# DC_DC_V1_4_2-1_top_with_comments.net
KiCad netlist of a schematic drawn in EAGLE
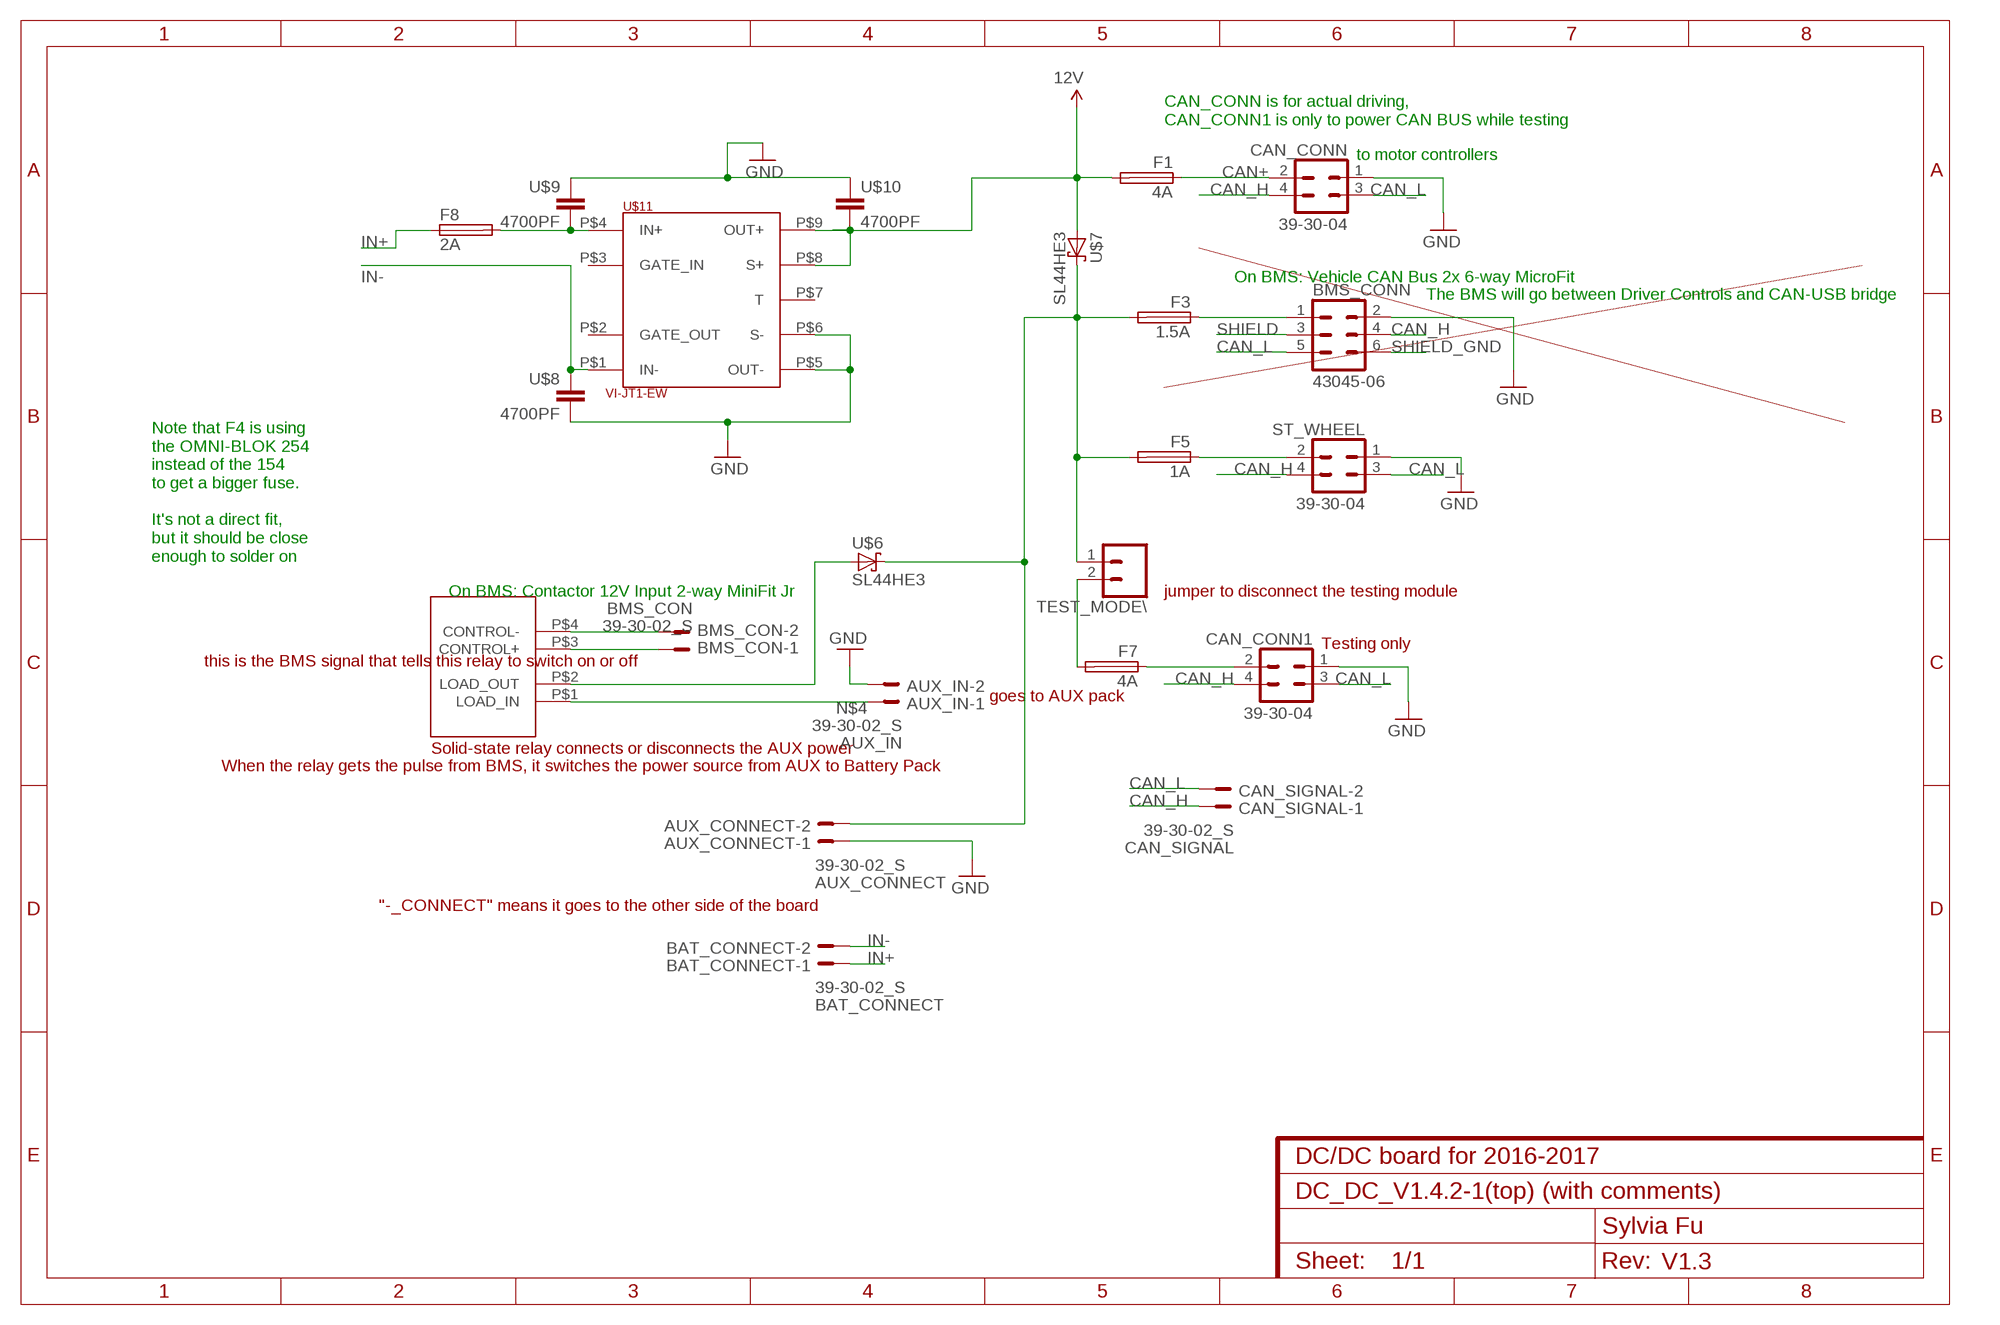
[diagram p0: schematic, sheet 1]

(export (version "E")
  (design (tool "Eeschema 10.0.6"))
  (components
    (comp (ref "AUX_CONNECT")
      (value "39-30-02_S")
      (footprint "eagle-import:39-30-_02_")
      (libsource (lib "eagle-import") (part "39-30-?02?_S"))
    )
    (comp (ref "AUX_IN")
      (value "39-30-02_S")
      (footprint "eagle-import:39-30-_02_")
      (libsource (lib "eagle-import") (part "39-30-?02?_S"))
    )
    (comp (ref "BAT_CONNECT")
      (value "39-30-02_S")
      (footprint "eagle-import:39-30-_02_")
      (libsource (lib "eagle-import") (part "39-30-?02?_S"))
    )
    (comp (ref "BMS_CON")
      (value "39-30-02_S")
      (footprint "eagle-import:39-30-_02_")
      (libsource (lib "eagle-import") (part "39-30-?02?_S"))
    )
    (comp (ref "BMS_CONN")
      (value "43045-06")
      (footprint "eagle-import:43045-06")
      (libsource (lib "eagle-import") (part "43045-06"))
    )
    (comp (ref "CAN_CONN")
      (value "39-30-04")
      (footprint "eagle-import:39-30-_04_")
      (libsource (lib "eagle-import") (part "39-30-?04?"))
    )
    (comp (ref "CAN_CONN1")
      (value "39-30-04")
      (footprint "eagle-import:39-30-_04_")
      (libsource (lib "eagle-import") (part "39-30-?04?"))
    )
    (comp (ref "CAN_SIGNAL")
      (value "39-30-02_S")
      (footprint "eagle-import:39-30-_02_")
      (libsource (lib "eagle-import") (part "39-30-?02?_S"))
    )
    (comp (ref "F1")
      (value "4A")
      (footprint "eagle-import:OMNIBLOK")
      (libsource (lib "eagle-import") (part "SMD-MICRO-FUSE-BLOCK"))
    )
    (comp (ref "F3")
      (value "1.5A")
      (footprint "eagle-import:OMNIBLOK")
      (libsource (lib "eagle-import") (part "SMD-MICRO-FUSE-BLOCK"))
    )
    (comp (ref "F5")
      (value "1A")
      (footprint "eagle-import:OMNIBLOK")
      (libsource (lib "eagle-import") (part "SMD-MICRO-FUSE-BLOCK"))
    )
    (comp (ref "F7")
      (value "4A")
      (footprint "eagle-import:OMNIBLOK")
      (libsource (lib "eagle-import") (part "SMD-MICRO-FUSE-BLOCK"))
    )
    (comp (ref "F8")
      (value "2A")
      (footprint "eagle-import:OMNIBLOK")
      (libsource (lib "eagle-import") (part "SMD-MICRO-FUSE-BLOCK"))
    )
    (comp (ref "ST_WHEEL")
      (value "39-30-04")
      (footprint "eagle-import:39-30-_04_")
      (libsource (lib "eagle-import") (part "39-30-?04?"))
    )
    (comp (ref "TEST_MODE\\")
      (value "CONN_02")
      (footprint "eagle-import:1X02")
      (libsource (lib "eagle-import") (part "CONN_02"))
    )
    (comp (ref "U$2")
      (value "MPDCD3B")
      (footprint "eagle-import:MPDCD3B")
      (libsource (lib "eagle-import") (part "MPDCD3B"))
    )
    (comp (ref "U$6")
      (value "SL44HE3")
      (footprint "eagle-import:SMC")
      (libsource (lib "eagle-import") (part "SL44HE3"))
    )
    (comp (ref "U$7")
      (value "SL44HE3")
      (footprint "eagle-import:SMC")
      (libsource (lib "eagle-import") (part "SL44HE3"))
    )
    (comp (ref "U$8")
      (value "4700PF")
      (footprint "eagle-import:Y2_CAP")
      (libsource (lib "eagle-import") (part "4700PF"))
    )
    (comp (ref "U$9")
      (value "4700PF")
      (footprint "eagle-import:Y2_CAP")
      (libsource (lib "eagle-import") (part "4700PF"))
    )
    (comp (ref "U$10")
      (value "4700PF")
      (footprint "eagle-import:Y2_CAP")
      (libsource (lib "eagle-import") (part "4700PF"))
    )
    (comp (ref "U$11")
      (value "VI-JT1-EW")
      (footprint "eagle-import:VI-J00")
      (libsource (lib "eagle-import") (part "VI-JT1-EW"))
    )
  )
  (nets
    (net (code "1") (name "/CAN+") (class "Default")
      (node (ref "CAN_CONN") (pin "2") (pinfunction "2_2") (pintype "passive"))
      (node (ref "F1") (pin "P$1") (pinfunction "1_P$1") (pintype "passive"))
    )
    (net (code "2") (name "/CAN_H") (class "Default")
      (node (ref "BMS_CONN") (pin "4") (pinfunction "4_4") (pintype "passive"))
      (node (ref "CAN_CONN") (pin "4") (pinfunction "4_4") (pintype "passive"))
      (node (ref "CAN_CONN1") (pin "4") (pinfunction "4_4") (pintype "passive"))
      (node (ref "CAN_SIGNAL") (pin "1") (pinfunction "P_1") (pintype "passive"))
      (node (ref "ST_WHEEL") (pin "4") (pinfunction "4_4") (pintype "passive"))
    )
    (net (code "3") (name "/CAN_L") (class "Default")
      (node (ref "BMS_CONN") (pin "5") (pinfunction "5_5") (pintype "passive"))
      (node (ref "CAN_CONN") (pin "3") (pinfunction "3_3") (pintype "passive"))
      (node (ref "CAN_CONN1") (pin "3") (pinfunction "3_3") (pintype "passive"))
      (node (ref "CAN_SIGNAL") (pin "2") (pinfunction "P_2") (pintype "passive"))
      (node (ref "ST_WHEEL") (pin "3") (pinfunction "3_3") (pintype "passive"))
    )
    (net (code "4") (name "/IN+") (class "Default")
      (node (ref "BAT_CONNECT") (pin "1") (pinfunction "P_1") (pintype "passive"))
      (node (ref "F8") (pin "P$1") (pinfunction "1_P$1") (pintype "passive"))
    )
    (net (code "5") (name "/IN-") (class "Default")
      (node (ref "BAT_CONNECT") (pin "2") (pinfunction "P_2") (pintype "passive"))
      (node (ref "U$11") (pin "P$1") (pinfunction "IN-_P$1") (pintype "bidirectional"))
      (node (ref "U$8") (pin "P$1") (pinfunction "1_P$1") (pintype "passive"))
    )
    (net (code "6") (name "/N$4") (class "Default")
      (node (ref "U$2") (pin "P$2") (pinfunction "LOAD_OUT_P$2") (pintype "bidirectional"))
      (node (ref "U$6") (pin "A") (pinfunction "A_A") (pintype "passive"))
    )
    (net (code "7") (name "/SHIELD") (class "Default")
      (node (ref "BMS_CONN") (pin "3") (pinfunction "3_3") (pintype "passive"))
    )
    (net (code "8") (name "/SHIELD_GND") (class "Default")
      (node (ref "BMS_CONN") (pin "6") (pinfunction "6_6") (pintype "passive"))
    )
    (net (code "9") (name "12V") (class "Default")
      (node (ref "F1") (pin "P$2") (pinfunction "2_P$2") (pintype "passive"))
      (node (ref "U$10") (pin "P$2") (pinfunction "2_P$2") (pintype "passive"))
      (node (ref "U$11") (pin "P$8") (pinfunction "S+_P$8") (pintype "bidirectional"))
      (node (ref "U$11") (pin "P$9") (pinfunction "OUT+_P$9") (pintype "bidirectional"))
      (node (ref "U$7") (pin "A") (pinfunction "A_A") (pintype "passive"))
    )
    (net (code "10") (name "GND") (class "Default")
      (node (ref "AUX_CONNECT") (pin "1") (pinfunction "P_1") (pintype "passive"))
      (node (ref "AUX_IN") (pin "2") (pinfunction "P_2") (pintype "passive"))
      (node (ref "BMS_CONN") (pin "2") (pinfunction "2_2") (pintype "passive"))
      (node (ref "CAN_CONN") (pin "1") (pinfunction "1_1") (pintype "passive"))
      (node (ref "CAN_CONN1") (pin "1") (pinfunction "1_1") (pintype "passive"))
      (node (ref "ST_WHEEL") (pin "1") (pinfunction "1_1") (pintype "passive"))
      (node (ref "U$10") (pin "P$1") (pinfunction "1_P$1") (pintype "passive"))
      (node (ref "U$11") (pin "P$5") (pinfunction "OUT-_P$5") (pintype "bidirectional"))
      (node (ref "U$11") (pin "P$6") (pinfunction "S-_P$6") (pintype "bidirectional"))
      (node (ref "U$8") (pin "P$2") (pinfunction "2_P$2") (pintype "passive"))
      (node (ref "U$9") (pin "P$1") (pinfunction "1_P$1") (pintype "passive"))
    )
    (net (code "11") (name "Net-(AUX_CONNECTB-P)") (class "Default")
      (node (ref "AUX_CONNECT") (pin "2") (pinfunction "P_2") (pintype "passive"))
      (node (ref "F3") (pin "P$2") (pinfunction "2_P$2") (pintype "passive"))
      (node (ref "F5") (pin "P$2") (pinfunction "2_P$2") (pintype "passive"))
      (node (ref "TEST_MODE\\") (pin "1") (pinfunction "1_1") (pintype "passive"))
      (node (ref "U$6") (pin "C") (pinfunction "C_C") (pintype "passive"))
      (node (ref "U$7") (pin "C") (pinfunction "C_C") (pintype "passive"))
    )
    (net (code "12") (name "Net-(AUX_INA-P)") (class "Default")
      (node (ref "AUX_IN") (pin "1") (pinfunction "P_1") (pintype "passive"))
      (node (ref "U$2") (pin "P$1") (pinfunction "LOAD_IN_P$1") (pintype "bidirectional"))
    )
    (net (code "13") (name "Net-(BMS_CONA-P)") (class "Default")
      (node (ref "BMS_CON") (pin "1") (pinfunction "P_1") (pintype "passive"))
      (node (ref "U$2") (pin "P$3") (pinfunction "CONTROL+_P$3") (pintype "bidirectional"))
    )
    (net (code "14") (name "Net-(BMS_CONB-P)") (class "Default")
      (node (ref "BMS_CON") (pin "2") (pinfunction "P_2") (pintype "passive"))
      (node (ref "U$2") (pin "P$4") (pinfunction "CONTROL-_P$4") (pintype "bidirectional"))
    )
    (net (code "15") (name "Net-(F3-1)") (class "Default")
      (node (ref "BMS_CONN") (pin "1") (pinfunction "1_1") (pintype "passive"))
      (node (ref "F3") (pin "P$1") (pinfunction "1_P$1") (pintype "passive"))
    )
    (net (code "16") (name "Net-(F5-1)") (class "Default")
      (node (ref "F5") (pin "P$1") (pinfunction "1_P$1") (pintype "passive"))
      (node (ref "ST_WHEEL") (pin "2") (pinfunction "2_2") (pintype "passive"))
    )
    (net (code "17") (name "Net-(F7-1)") (class "Default")
      (node (ref "CAN_CONN1") (pin "2") (pinfunction "2_2") (pintype "passive"))
      (node (ref "F7") (pin "P$1") (pinfunction "1_P$1") (pintype "passive"))
    )
    (net (code "18") (name "Net-(F7-2)") (class "Default")
      (node (ref "F7") (pin "P$2") (pinfunction "2_P$2") (pintype "passive"))
      (node (ref "TEST_MODE\\") (pin "2") (pinfunction "2_2") (pintype "passive"))
    )
    (net (code "19") (name "Net-(F8-2)") (class "Default")
      (node (ref "F8") (pin "P$2") (pinfunction "2_P$2") (pintype "passive"))
      (node (ref "U$11") (pin "P$4") (pinfunction "IN+_P$4") (pintype "bidirectional"))
      (node (ref "U$9") (pin "P$2") (pinfunction "2_P$2") (pintype "passive"))
    )
    (net (code "20") (name "unconnected-(U$11-GATE_IN-PadP$3)") (class "Default")
      (node (ref "U$11") (pin "P$3") (pinfunction "GATE_IN_P$3") (pintype "bidirectional"))
    )
    (net (code "21") (name "unconnected-(U$11-GATE_OUT-PadP$2)") (class "Default")
      (node (ref "U$11") (pin "P$2") (pinfunction "GATE_OUT_P$2") (pintype "bidirectional"))
    )
    (net (code "22") (name "unconnected-(U$11-T-PadP$7)") (class "Default")
      (node (ref "U$11") (pin "P$7") (pinfunction "T_P$7") (pintype "bidirectional"))
    )
  )
)
